# section3.net
KiCad netlist of a schematic drawn in EasyEDA
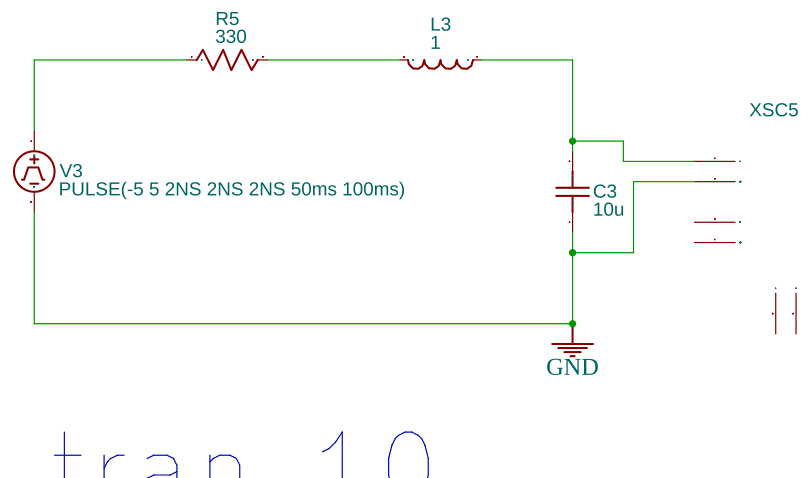
[diagram p0: schematic sheet]

(export (version "E")
  (design (tool "Eeschema 10.0.6"))
  (components
    (comp (ref "C3") (value "10u") (libsource (lib "") (part "Capacitor_US")))
    (comp (ref "L3") (value "1") (libsource (lib "") (part "Inductor")))
    (comp (ref "R5") (value "330") (libsource (lib "") (part "Resistor_US")))
    (comp (ref "V3") (value "PULSE(-5 5 2NS 2NS 2NS 50ms 100ms)") (libsource (lib "") (part "VPULSE")))
    (comp (ref "XSC5") (value "Oscilloscope") (libsource (lib "") (part "OSCILLOSCOPE")))
  )
  (nets
    (net (code "1") (name "GND") (class "Default")
      (node (ref "C3") (pin "1") (pinfunction "1_1") (pintype "unspecified"))
      (node (ref "V3") (pin "2") (pinfunction "2_2") (pintype "unspecified"))
      (node (ref "XSC5") (pin "2") (pinfunction "GND1_2") (pintype "unspecified"))
    )
    (net (code "2") (name "Net-(L3-Pad2)") (class "Default")
      (node (ref "L3") (pin "2") (pinfunction "2_2") (pintype "unspecified"))
      (node (ref "R5") (pin "2") (pinfunction "2_2") (pintype "unspecified"))
    )
    (net (code "3") (name "Net-(R5-Pad1)") (class "Default")
      (node (ref "R5") (pin "1") (pinfunction "1_1") (pintype "unspecified"))
      (node (ref "V3") (pin "1") (pinfunction "1_1") (pintype "unspecified"))
    )
    (net (code "4") (name "Net-(XSC5-A)") (class "Default")
      (node (ref "C3") (pin "2") (pinfunction "2_2") (pintype "unspecified"))
      (node (ref "L3") (pin "1") (pinfunction "1_1") (pintype "unspecified"))
      (node (ref "XSC5") (pin "1") (pinfunction "A_1") (pintype "unspecified"))
    )
    (net (code "5") (name "unconnected-(XSC5-B-Pad3)") (class "Default")
      (node (ref "XSC5") (pin "3") (pinfunction "B_3") (pintype "unspecified"))
    )
    (net (code "6") (name "unconnected-(XSC5-GND2-Pad4)") (class "Default")
      (node (ref "XSC5") (pin "4") (pinfunction "GND2_4") (pintype "unspecified"))
    )
    (net (code "7") (name "unconnected-(XSC5-T+-Pad5)") (class "Default")
      (node (ref "XSC5") (pin "5") (pinfunction "T+_5") (pintype "unspecified"))
    )
    (net (code "8") (name "unconnected-(XSC5-T--Pad6)") (class "Default")
      (node (ref "XSC5") (pin "6") (pinfunction "T-_6") (pintype "unspecified"))
    )
  )
)
